# Sheet1.net
KiCad netlist of a schematic drawn in Altium Designer
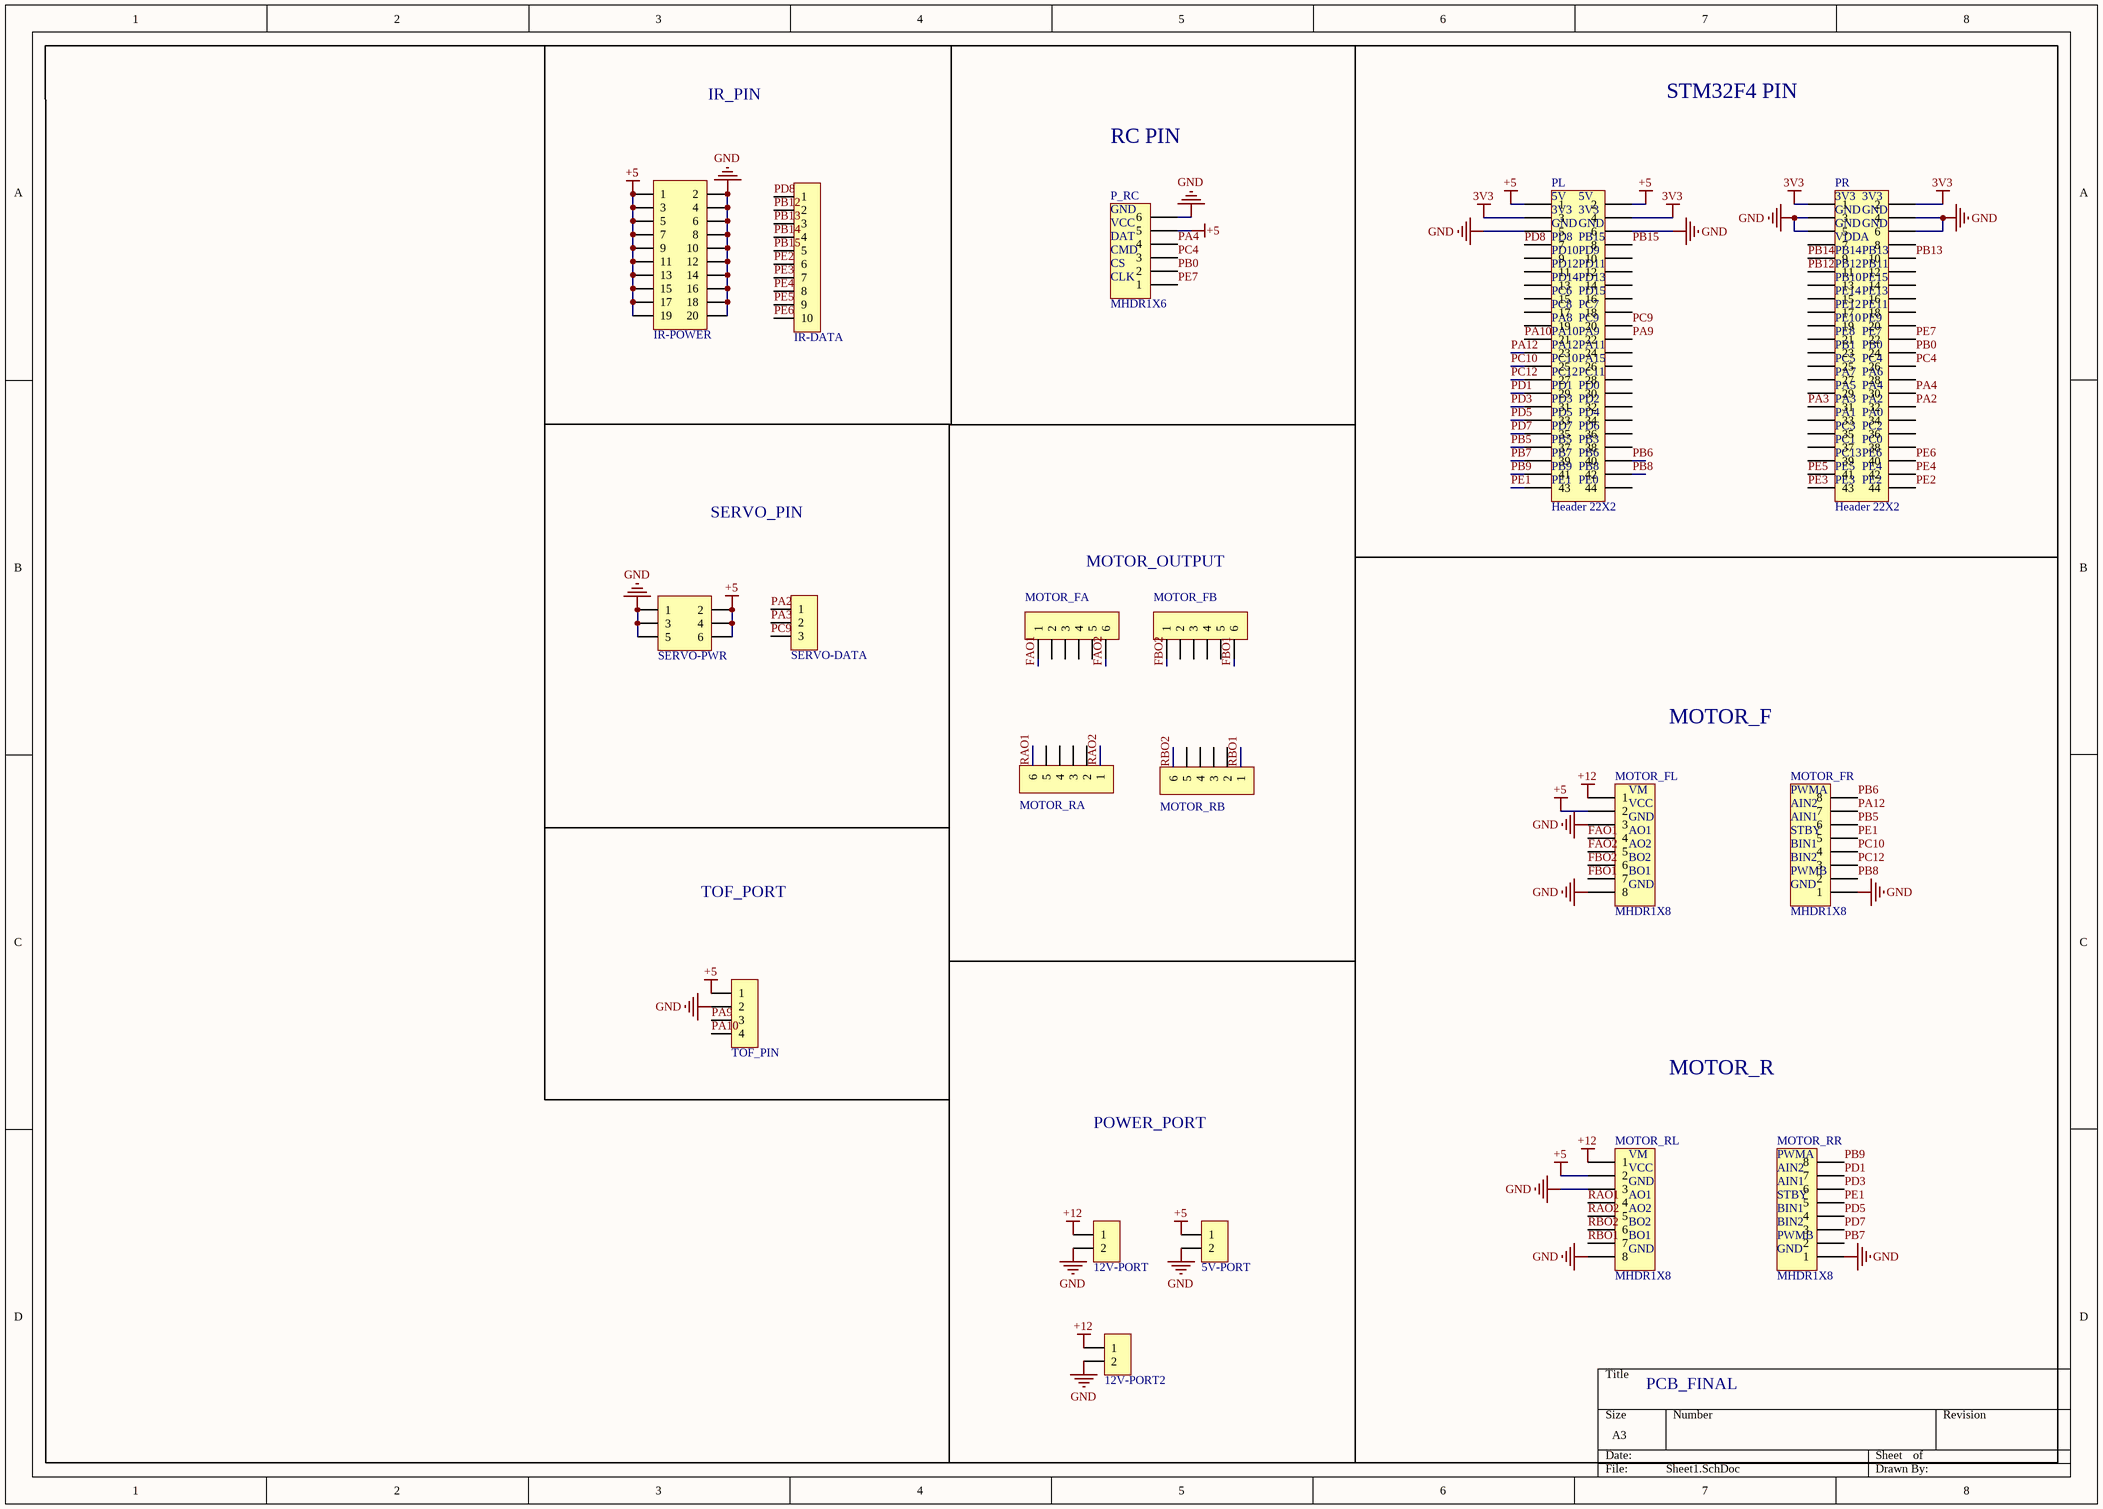
[diagram p0: Sheet1.SchDoc]

(export (version "E")
  (design (tool "Eeschema 10.0.6"))
  (components
    (comp (ref "5V-PORT")
      (value "HDR-1X2")
      (footprint "KF301-5.0-2P")
      (description "2P接插件")
      (fields (field (name "版权归属") "封装库来自淘宝卖家 ID：黄晶宝石"))
      (libsource (lib "6.1 - 接插件-脚距5.08 (200mil) ") (part "Header 2"))
    )
    (comp (ref "12V-PORT")
      (value "HDR-1X2")
      (footprint "KF301-5.0-2P")
      (description "2P接插件")
      (fields (field (name "版权归属") "封装库来自淘宝卖家 ID：黄晶宝石"))
      (libsource (lib "6.1 - 接插件-脚距5.08 (200mil) ") (part "Header 2"))
    )
    (comp (ref "12V-PORT2")
      (value "HDR-1X2")
      (footprint "KF301-5.0-2P")
      (description "2P接插件")
      (fields (field (name "版权归属") "封装库来自淘宝卖家 ID：黄晶宝石"))
      (libsource (lib "6.1 - 接插件-脚距5.08 (200mil) ") (part "Header 2"))
    )
    (comp (ref "IR-DATA")
      (value "HDR-1X10")
      (footprint "HDR2.54-LI-10P")
      (description "10P接插件")
      (fields (field (name "版权归属") "淘宝ID:黄晶宝石"))
      (libsource (lib "5.4 - 接插件-脚距2.54 (100mil) ") (part "Header 10"))
    )
    (comp (ref "IR-POWER")
      (value "Header 2X10")
      (footprint "HDR2.54-LI-2x10P")
      (description "10*2P接插件")
      (fields (field (name "版权归属") "源创客"))
      (libsource (lib "5.4 - 接插件-脚距2.54 (100mil) ") (part "Header 10X2"))
    )
    (comp (ref "MOTOR_FA")
      (value "HDR-1X6")
      (footprint "PH2.0-LI-6P")
      (description "6P接插件")
      (libsource (lib "") (part "Header 6_1"))
    )
    (comp (ref "MOTOR_FB")
      (value "HDR-1X6")
      (footprint "PH2.0-LI-6P")
      (description "6P接插件")
      (libsource (lib "") (part "Header 6_1"))
    )
    (comp (ref "MOTOR_FL")
      (value "MHDR1X8")
      (footprint "HDR2.54-M-LI-8P")
      (description "Header, 8-Pin")
      (fields (field (name "PUBLISHER") "Altium Limited"))
      (libsource (lib "Miscellaneous Connectors") (part "MHDR1X8"))
    )
    (comp (ref "MOTOR_FR")
      (value "MHDR1X8")
      (footprint "HDR2.54-M-LI-8P")
      (description "Header, 8-Pin")
      (fields (field (name "PUBLISHER") "Altium Limited"))
      (libsource (lib "") (part "MHDR1X8_1"))
    )
    (comp (ref "MOTOR_RA")
      (value "HDR-1X6")
      (footprint "PH2.0-LI-6P")
      (description "6P接插件")
      (libsource (lib "5.3 - 接插件-脚距2.0") (part "Header 6"))
    )
    (comp (ref "MOTOR_RB")
      (value "HDR-1X6")
      (footprint "PH2.0-LI-6P")
      (description "6P接插件")
      (libsource (lib "5.3 - 接插件-脚距2.0") (part "Header 6"))
    )
    (comp (ref "MOTOR_RL")
      (value "MHDR1X8")
      (footprint "HDR2.54-M-LI-8P")
      (description "Header, 8-Pin")
      (fields (field (name "PUBLISHER") "Altium Limited"))
      (libsource (lib "Miscellaneous Connectors") (part "MHDR1X8"))
    )
    (comp (ref "MOTOR_RR")
      (value "MHDR1X8")
      (footprint "HDR2.54-M-LI-8P")
      (description "Header, 8-Pin")
      (fields (field (name "PUBLISHER") "Altium Limited"))
      (libsource (lib "") (part "MHDR1X8_1"))
    )
    (comp (ref "PL")
      (value "Header 22X2")
      (footprint "P_M_2x22P")
      (description "Header, 22-Pin, Dual row")
      (fields (field (name "PUBLISHER") "Altium Limited"))
      (libsource (lib "Miscellaneous Connectors") (part "Header 22X2"))
    )
    (comp (ref "PR")
      (value "Header 22X2")
      (footprint "P_M_2x22P")
      (description "Header, 22-Pin, Dual row")
      (fields (field (name "PUBLISHER") "Altium Limited"))
      (libsource (lib "Miscellaneous Connectors") (part "Header 22X2"))
    )
    (comp (ref "P_RC")
      (value "MHDR1X6")
      (footprint "4.02-2.54mm排针-排母:HDR2.54-M-LI-6P")
      (description "Header, 6-Pin")
      (fields (field (name "PUBLISHER") "Altium Limited"))
      (libsource (lib "Miscellaneous Connectors") (part "MHDR1X6"))
    )
    (comp (ref "SERVO-DATA")
      (value "HDR-1X3")
      (footprint "HDR2.54-LI-3P")
      (description "3P接插件")
      (fields (field (name "版权归属") "封装库来自淘宝 ID：黄晶宝石"))
      (libsource (lib "5.4 - 接插件-脚距2.54 (100mil) ") (part "Header 3"))
    )
    (comp (ref "SERVO-PWR")
      (value "Header3X2")
      (footprint "HDR2.54-LI-2x3P")
      (description "3*2P接插件")
      (fields (field (name "版权归属") "封装库来自淘宝 ID：黄晶宝石"))
      (libsource (lib "5.4 - 接插件-脚距2.54 (100mil) ") (part "Header 3X2"))
    )
    (comp (ref "TOF_PIN")
      (value "HDR-1X4")
      (footprint "HDR2.54-LI-4P")
      (description "4P接插件")
      (fields (field (name "版权归属") "封装库来自淘宝 ID：黄晶宝石"))
      (libsource (lib "5.4 - 接插件-脚距2.54 (100mil) ") (part "Header 4"))
    )
  )
  (nets
    (net (code "1") (name "+5") (class "Default")
      (node (ref "5V-PORT") (pin "1") (pinfunction "1_1") (pintype "passive"))
      (node (ref "IR-POWER") (pin "1") (pinfunction "1_1") (pintype "passive"))
      (node (ref "IR-POWER") (pin "11") (pinfunction "11_11") (pintype "passive"))
      (node (ref "IR-POWER") (pin "13") (pinfunction "13_13") (pintype "passive"))
      (node (ref "IR-POWER") (pin "15") (pinfunction "15_15") (pintype "passive"))
      (node (ref "IR-POWER") (pin "17") (pinfunction "17_17") (pintype "passive"))
      (node (ref "IR-POWER") (pin "19") (pinfunction "19_19") (pintype "passive"))
      (node (ref "IR-POWER") (pin "3") (pinfunction "3_3") (pintype "passive"))
      (node (ref "IR-POWER") (pin "5") (pinfunction "5_5") (pintype "passive"))
      (node (ref "IR-POWER") (pin "7") (pinfunction "7_7") (pintype "passive"))
      (node (ref "IR-POWER") (pin "9") (pinfunction "9_9") (pintype "passive"))
      (node (ref "MOTOR_FL") (pin "2") (pinfunction "2_2") (pintype "passive"))
      (node (ref "MOTOR_RL") (pin "2") (pinfunction "2_2") (pintype "passive"))
      (node (ref "PL") (pin "1") (pinfunction "1_1") (pintype "passive"))
      (node (ref "PL") (pin "2") (pinfunction "2_2") (pintype "passive"))
      (node (ref "P_RC") (pin "5") (pinfunction "5_5") (pintype "passive"))
      (node (ref "SERVO-PWR") (pin "2") (pinfunction "2_2") (pintype "passive"))
      (node (ref "SERVO-PWR") (pin "4") (pinfunction "4_4") (pintype "passive"))
      (node (ref "SERVO-PWR") (pin "6") (pinfunction "6_6") (pintype "passive"))
      (node (ref "TOF_PIN") (pin "1") (pinfunction "1_1") (pintype "passive"))
    )
    (net (code "2") (name "+12") (class "Default")
      (node (ref "12V-PORT") (pin "1") (pinfunction "1_1") (pintype "passive"))
      (node (ref "12V-PORT2") (pin "1") (pinfunction "1_1") (pintype "passive"))
      (node (ref "MOTOR_FL") (pin "1") (pinfunction "1_1") (pintype "passive"))
      (node (ref "MOTOR_RL") (pin "1") (pinfunction "1_1") (pintype "passive"))
    )
    (net (code "3") (name "/FAO1") (class "Default")
      (node (ref "MOTOR_FA") (pin "1") (pinfunction "1_1") (pintype "passive"))
      (node (ref "MOTOR_FL") (pin "4") (pinfunction "4_4") (pintype "passive"))
    )
    (net (code "4") (name "/FAO2") (class "Default")
      (node (ref "MOTOR_FA") (pin "6") (pinfunction "6_6") (pintype "passive"))
      (node (ref "MOTOR_FL") (pin "5") (pinfunction "5_5") (pintype "passive"))
    )
    (net (code "5") (name "/FBO1") (class "Default")
      (node (ref "MOTOR_FB") (pin "6") (pinfunction "6_6") (pintype "passive"))
      (node (ref "MOTOR_FL") (pin "7") (pinfunction "7_7") (pintype "passive"))
    )
    (net (code "6") (name "/FBO2") (class "Default")
      (node (ref "MOTOR_FB") (pin "1") (pinfunction "1_1") (pintype "passive"))
      (node (ref "MOTOR_FL") (pin "6") (pinfunction "6_6") (pintype "passive"))
    )
    (net (code "7") (name "/PA2") (class "Default")
      (node (ref "PR") (pin "32") (pinfunction "32_32") (pintype "passive"))
      (node (ref "SERVO-DATA") (pin "1") (pinfunction "1_1") (pintype "passive"))
    )
    (net (code "8") (name "/PA3") (class "Default")
      (node (ref "PR") (pin "31") (pinfunction "31_31") (pintype "passive"))
      (node (ref "SERVO-DATA") (pin "2") (pinfunction "2_2") (pintype "passive"))
    )
    (net (code "9") (name "/PA4") (class "Default")
      (node (ref "PR") (pin "30") (pinfunction "30_30") (pintype "passive"))
      (node (ref "P_RC") (pin "4") (pinfunction "4_4") (pintype "passive"))
    )
    (net (code "10") (name "/PA9") (class "Default")
      (node (ref "PL") (pin "22") (pinfunction "22_22") (pintype "passive"))
      (node (ref "TOF_PIN") (pin "3") (pinfunction "3_3") (pintype "passive"))
    )
    (net (code "11") (name "/PA10") (class "Default")
      (node (ref "PL") (pin "21") (pinfunction "21_21") (pintype "passive"))
      (node (ref "TOF_PIN") (pin "4") (pinfunction "4_4") (pintype "passive"))
    )
    (net (code "12") (name "/PA12") (class "Default")
      (node (ref "MOTOR_FR") (pin "7") (pinfunction "7_7") (pintype "passive"))
      (node (ref "PL") (pin "23") (pinfunction "23_23") (pintype "passive"))
    )
    (net (code "13") (name "/PB0") (class "Default")
      (node (ref "PR") (pin "24") (pinfunction "24_24") (pintype "passive"))
      (node (ref "P_RC") (pin "2") (pinfunction "2_2") (pintype "passive"))
    )
    (net (code "14") (name "/PB5") (class "Default")
      (node (ref "MOTOR_FR") (pin "6") (pinfunction "6_6") (pintype "passive"))
      (node (ref "PL") (pin "37") (pinfunction "37_37") (pintype "passive"))
    )
    (net (code "15") (name "/PB6") (class "Default")
      (node (ref "MOTOR_FR") (pin "8") (pinfunction "8_8") (pintype "passive"))
      (node (ref "PL") (pin "40") (pinfunction "40_40") (pintype "passive"))
    )
    (net (code "16") (name "/PB7") (class "Default")
      (node (ref "MOTOR_RR") (pin "2") (pinfunction "2_2") (pintype "passive"))
      (node (ref "PL") (pin "39") (pinfunction "39_39") (pintype "passive"))
    )
    (net (code "17") (name "/PB8") (class "Default")
      (node (ref "MOTOR_FR") (pin "2") (pinfunction "2_2") (pintype "passive"))
      (node (ref "PL") (pin "42") (pinfunction "42_42") (pintype "passive"))
    )
    (net (code "18") (name "/PB9") (class "Default")
      (node (ref "MOTOR_RR") (pin "8") (pinfunction "8_8") (pintype "passive"))
      (node (ref "PL") (pin "41") (pinfunction "41_41") (pintype "passive"))
    )
    (net (code "19") (name "/PB12") (class "Default")
      (node (ref "IR-DATA") (pin "2") (pinfunction "2_2") (pintype "passive"))
      (node (ref "PR") (pin "11") (pinfunction "11_11") (pintype "passive"))
    )
    (net (code "20") (name "/PB13") (class "Default")
      (node (ref "IR-DATA") (pin "3") (pinfunction "3_3") (pintype "passive"))
      (node (ref "PR") (pin "10") (pinfunction "10_10") (pintype "passive"))
    )
    (net (code "21") (name "/PB14") (class "Default")
      (node (ref "IR-DATA") (pin "4") (pinfunction "4_4") (pintype "passive"))
      (node (ref "PR") (pin "9") (pinfunction "9_9") (pintype "passive"))
    )
    (net (code "22") (name "/PB15") (class "Default")
      (node (ref "IR-DATA") (pin "5") (pinfunction "5_5") (pintype "passive"))
      (node (ref "PL") (pin "8") (pinfunction "8_8") (pintype "passive"))
    )
    (net (code "23") (name "/PC4") (class "Default")
      (node (ref "PR") (pin "26") (pinfunction "26_26") (pintype "passive"))
      (node (ref "P_RC") (pin "3") (pinfunction "3_3") (pintype "passive"))
    )
    (net (code "24") (name "/PC9") (class "Default")
      (node (ref "PL") (pin "20") (pinfunction "20_20") (pintype "passive"))
      (node (ref "SERVO-DATA") (pin "3") (pinfunction "3_3") (pintype "passive"))
    )
    (net (code "25") (name "/PC10") (class "Default")
      (node (ref "MOTOR_FR") (pin "4") (pinfunction "4_4") (pintype "passive"))
      (node (ref "PL") (pin "25") (pinfunction "25_25") (pintype "passive"))
    )
    (net (code "26") (name "/PC12") (class "Default")
      (node (ref "MOTOR_FR") (pin "3") (pinfunction "3_3") (pintype "passive"))
      (node (ref "PL") (pin "27") (pinfunction "27_27") (pintype "passive"))
    )
    (net (code "27") (name "/PD1") (class "Default")
      (node (ref "MOTOR_RR") (pin "7") (pinfunction "7_7") (pintype "passive"))
      (node (ref "PL") (pin "29") (pinfunction "29_29") (pintype "passive"))
    )
    (net (code "28") (name "/PD3") (class "Default")
      (node (ref "MOTOR_RR") (pin "6") (pinfunction "6_6") (pintype "passive"))
      (node (ref "PL") (pin "31") (pinfunction "31_31") (pintype "passive"))
    )
    (net (code "29") (name "/PD5") (class "Default")
      (node (ref "MOTOR_RR") (pin "4") (pinfunction "4_4") (pintype "passive"))
      (node (ref "PL") (pin "33") (pinfunction "33_33") (pintype "passive"))
    )
    (net (code "30") (name "/PD7") (class "Default")
      (node (ref "MOTOR_RR") (pin "3") (pinfunction "3_3") (pintype "passive"))
      (node (ref "PL") (pin "35") (pinfunction "35_35") (pintype "passive"))
    )
    (net (code "31") (name "/PD8") (class "Default")
      (node (ref "IR-DATA") (pin "1") (pinfunction "1_1") (pintype "passive"))
      (node (ref "PL") (pin "7") (pinfunction "7_7") (pintype "passive"))
    )
    (net (code "32") (name "/PE1") (class "Default")
      (node (ref "MOTOR_FR") (pin "5") (pinfunction "5_5") (pintype "passive"))
      (node (ref "MOTOR_RR") (pin "5") (pinfunction "5_5") (pintype "passive"))
      (node (ref "PL") (pin "43") (pinfunction "43_43") (pintype "passive"))
    )
    (net (code "33") (name "/PE2") (class "Default")
      (node (ref "IR-DATA") (pin "6") (pinfunction "6_6") (pintype "passive"))
      (node (ref "PR") (pin "44") (pinfunction "44_44") (pintype "passive"))
    )
    (net (code "34") (name "/PE3") (class "Default")
      (node (ref "IR-DATA") (pin "7") (pinfunction "7_7") (pintype "passive"))
      (node (ref "PR") (pin "43") (pinfunction "43_43") (pintype "passive"))
    )
    (net (code "35") (name "/PE4") (class "Default")
      (node (ref "IR-DATA") (pin "8") (pinfunction "8_8") (pintype "passive"))
      (node (ref "PR") (pin "42") (pinfunction "42_42") (pintype "passive"))
    )
    (net (code "36") (name "/PE5") (class "Default")
      (node (ref "IR-DATA") (pin "9") (pinfunction "9_9") (pintype "passive"))
      (node (ref "PR") (pin "41") (pinfunction "41_41") (pintype "passive"))
    )
    (net (code "37") (name "/PE6") (class "Default")
      (node (ref "IR-DATA") (pin "10") (pinfunction "10_10") (pintype "passive"))
      (node (ref "PR") (pin "40") (pinfunction "40_40") (pintype "passive"))
    )
    (net (code "38") (name "/PE7") (class "Default")
      (node (ref "PR") (pin "22") (pinfunction "22_22") (pintype "passive"))
      (node (ref "P_RC") (pin "1") (pinfunction "1_1") (pintype "passive"))
    )
    (net (code "39") (name "/RAO1") (class "Default")
      (node (ref "MOTOR_RA") (pin "6") (pinfunction "6_6") (pintype "passive"))
      (node (ref "MOTOR_RL") (pin "4") (pinfunction "4_4") (pintype "passive"))
    )
    (net (code "40") (name "/RAO2") (class "Default")
      (node (ref "MOTOR_RA") (pin "1") (pinfunction "1_1") (pintype "passive"))
      (node (ref "MOTOR_RL") (pin "5") (pinfunction "5_5") (pintype "passive"))
    )
    (net (code "41") (name "/RBO1") (class "Default")
      (node (ref "MOTOR_RB") (pin "1") (pinfunction "1_1") (pintype "passive"))
      (node (ref "MOTOR_RL") (pin "7") (pinfunction "7_7") (pintype "passive"))
    )
    (net (code "42") (name "/RBO2") (class "Default")
      (node (ref "MOTOR_RB") (pin "6") (pinfunction "6_6") (pintype "passive"))
      (node (ref "MOTOR_RL") (pin "6") (pinfunction "6_6") (pintype "passive"))
    )
    (net (code "43") (name "3V3") (class "Default")
      (node (ref "PL") (pin "3") (pinfunction "3_3") (pintype "passive"))
      (node (ref "PL") (pin "4") (pinfunction "4_4") (pintype "passive"))
      (node (ref "PR") (pin "1") (pinfunction "1_1") (pintype "passive"))
      (node (ref "PR") (pin "2") (pinfunction "2_2") (pintype "passive"))
    )
    (net (code "44") (name "GND") (class "Default")
      (node (ref "12V-PORT") (pin "2") (pinfunction "2_2") (pintype "passive"))
      (node (ref "12V-PORT2") (pin "2") (pinfunction "2_2") (pintype "passive"))
      (node (ref "5V-PORT") (pin "2") (pinfunction "2_2") (pintype "passive"))
      (node (ref "IR-POWER") (pin "10") (pinfunction "10_10") (pintype "passive"))
      (node (ref "IR-POWER") (pin "12") (pinfunction "12_12") (pintype "passive"))
      (node (ref "IR-POWER") (pin "14") (pinfunction "14_14") (pintype "passive"))
      (node (ref "IR-POWER") (pin "16") (pinfunction "16_16") (pintype "passive"))
      (node (ref "IR-POWER") (pin "18") (pinfunction "18_18") (pintype "passive"))
      (node (ref "IR-POWER") (pin "2") (pinfunction "2_2") (pintype "passive"))
      (node (ref "IR-POWER") (pin "20") (pinfunction "20_20") (pintype "passive"))
      (node (ref "IR-POWER") (pin "4") (pinfunction "4_4") (pintype "passive"))
      (node (ref "IR-POWER") (pin "6") (pinfunction "6_6") (pintype "passive"))
      (node (ref "IR-POWER") (pin "8") (pinfunction "8_8") (pintype "passive"))
      (node (ref "MOTOR_FL") (pin "3") (pinfunction "3_3") (pintype "passive"))
      (node (ref "MOTOR_FL") (pin "8") (pinfunction "8_8") (pintype "passive"))
      (node (ref "MOTOR_FR") (pin "1") (pinfunction "1_1") (pintype "passive"))
      (node (ref "MOTOR_RL") (pin "3") (pinfunction "3_3") (pintype "passive"))
      (node (ref "MOTOR_RL") (pin "8") (pinfunction "8_8") (pintype "passive"))
      (node (ref "MOTOR_RR") (pin "1") (pinfunction "1_1") (pintype "passive"))
      (node (ref "PL") (pin "5") (pinfunction "5_5") (pintype "passive"))
      (node (ref "PL") (pin "6") (pinfunction "6_6") (pintype "passive"))
      (node (ref "PR") (pin "3") (pinfunction "3_3") (pintype "passive"))
      (node (ref "PR") (pin "4") (pinfunction "4_4") (pintype "passive"))
      (node (ref "PR") (pin "5") (pinfunction "5_5") (pintype "passive"))
      (node (ref "PR") (pin "6") (pinfunction "6_6") (pintype "passive"))
      (node (ref "P_RC") (pin "6") (pinfunction "6_6") (pintype "passive"))
      (node (ref "SERVO-PWR") (pin "1") (pinfunction "1_1") (pintype "passive"))
      (node (ref "SERVO-PWR") (pin "3") (pinfunction "3_3") (pintype "passive"))
      (node (ref "SERVO-PWR") (pin "5") (pinfunction "5_5") (pintype "passive"))
      (node (ref "TOF_PIN") (pin "2") (pinfunction "2_2") (pintype "passive"))
    )
    (net (code "45") (name "unconnected-(MOTOR_FA-Pad2)") (class "Default")
      (node (ref "MOTOR_FA") (pin "2") (pinfunction "2_2") (pintype "passive"))
    )
    (net (code "46") (name "unconnected-(MOTOR_FA-Pad3)") (class "Default")
      (node (ref "MOTOR_FA") (pin "3") (pinfunction "3_3") (pintype "passive"))
    )
    (net (code "47") (name "unconnected-(MOTOR_FA-Pad4)") (class "Default")
      (node (ref "MOTOR_FA") (pin "4") (pinfunction "4_4") (pintype "passive"))
    )
    (net (code "48") (name "unconnected-(MOTOR_FA-Pad5)") (class "Default")
      (node (ref "MOTOR_FA") (pin "5") (pinfunction "5_5") (pintype "passive"))
    )
    (net (code "49") (name "unconnected-(MOTOR_FB-Pad2)") (class "Default")
      (node (ref "MOTOR_FB") (pin "2") (pinfunction "2_2") (pintype "passive"))
    )
    (net (code "50") (name "unconnected-(MOTOR_FB-Pad3)") (class "Default")
      (node (ref "MOTOR_FB") (pin "3") (pinfunction "3_3") (pintype "passive"))
    )
    (net (code "51") (name "unconnected-(MOTOR_FB-Pad4)") (class "Default")
      (node (ref "MOTOR_FB") (pin "4") (pinfunction "4_4") (pintype "passive"))
    )
    (net (code "52") (name "unconnected-(MOTOR_FB-Pad5)") (class "Default")
      (node (ref "MOTOR_FB") (pin "5") (pinfunction "5_5") (pintype "passive"))
    )
    (net (code "53") (name "unconnected-(MOTOR_RA-Pad2)") (class "Default")
      (node (ref "MOTOR_RA") (pin "2") (pinfunction "2_2") (pintype "passive"))
    )
    (net (code "54") (name "unconnected-(MOTOR_RA-Pad3)") (class "Default")
      (node (ref "MOTOR_RA") (pin "3") (pinfunction "3_3") (pintype "passive"))
    )
    (net (code "55") (name "unconnected-(MOTOR_RA-Pad4)") (class "Default")
      (node (ref "MOTOR_RA") (pin "4") (pinfunction "4_4") (pintype "passive"))
    )
    (net (code "56") (name "unconnected-(MOTOR_RA-Pad5)") (class "Default")
      (node (ref "MOTOR_RA") (pin "5") (pinfunction "5_5") (pintype "passive"))
    )
    (net (code "57") (name "unconnected-(MOTOR_RB-Pad2)") (class "Default")
      (node (ref "MOTOR_RB") (pin "2") (pinfunction "2_2") (pintype "passive"))
    )
    (net (code "58") (name "unconnected-(MOTOR_RB-Pad3)") (class "Default")
      (node (ref "MOTOR_RB") (pin "3") (pinfunction "3_3") (pintype "passive"))
    )
    (net (code "59") (name "unconnected-(MOTOR_RB-Pad4)") (class "Default")
      (node (ref "MOTOR_RB") (pin "4") (pinfunction "4_4") (pintype "passive"))
    )
    (net (code "60") (name "unconnected-(MOTOR_RB-Pad5)") (class "Default")
      (node (ref "MOTOR_RB") (pin "5") (pinfunction "5_5") (pintype "passive"))
    )
    (net (code "61") (name "unconnected-(PL-Pad9)") (class "Default")
      (node (ref "PL") (pin "9") (pinfunction "9_9") (pintype "passive"))
    )
    (net (code "62") (name "unconnected-(PL-Pad10)") (class "Default")
      (node (ref "PL") (pin "10") (pinfunction "10_10") (pintype "passive"))
    )
    (net (code "63") (name "unconnected-(PL-Pad11)") (class "Default")
      (node (ref "PL") (pin "11") (pinfunction "11_11") (pintype "passive"))
    )
    (net (code "64") (name "unconnected-(PL-Pad12)") (class "Default")
      (node (ref "PL") (pin "12") (pinfunction "12_12") (pintype "passive"))
    )
    (net (code "65") (name "unconnected-(PL-Pad13)") (class "Default")
      (node (ref "PL") (pin "13") (pinfunction "13_13") (pintype "passive"))
    )
    (net (code "66") (name "unconnected-(PL-Pad14)") (class "Default")
      (node (ref "PL") (pin "14") (pinfunction "14_14") (pintype "passive"))
    )
    (net (code "67") (name "unconnected-(PL-Pad15)") (class "Default")
      (node (ref "PL") (pin "15") (pinfunction "15_15") (pintype "passive"))
    )
    (net (code "68") (name "unconnected-(PL-Pad16)") (class "Default")
      (node (ref "PL") (pin "16") (pinfunction "16_16") (pintype "passive"))
    )
    (net (code "69") (name "unconnected-(PL-Pad17)") (class "Default")
      (node (ref "PL") (pin "17") (pinfunction "17_17") (pintype "passive"))
    )
    (net (code "70") (name "unconnected-(PL-Pad18)") (class "Default")
      (node (ref "PL") (pin "18") (pinfunction "18_18") (pintype "passive"))
    )
    (net (code "71") (name "unconnected-(PL-Pad19)") (class "Default")
      (node (ref "PL") (pin "19") (pinfunction "19_19") (pintype "passive"))
    )
    (net (code "72") (name "unconnected-(PL-Pad24)") (class "Default")
      (node (ref "PL") (pin "24") (pinfunction "24_24") (pintype "passive"))
    )
    (net (code "73") (name "unconnected-(PL-Pad26)") (class "Default")
      (node (ref "PL") (pin "26") (pinfunction "26_26") (pintype "passive"))
    )
    (net (code "74") (name "unconnected-(PL-Pad28)") (class "Default")
      (node (ref "PL") (pin "28") (pinfunction "28_28") (pintype "passive"))
    )
    (net (code "75") (name "unconnected-(PL-Pad30)") (class "Default")
      (node (ref "PL") (pin "30") (pinfunction "30_30") (pintype "passive"))
    )
    (net (code "76") (name "unconnected-(PL-Pad32)") (class "Default")
      (node (ref "PL") (pin "32") (pinfunction "32_32") (pintype "passive"))
    )
    (net (code "77") (name "unconnected-(PL-Pad34)") (class "Default")
      (node (ref "PL") (pin "34") (pinfunction "34_34") (pintype "passive"))
    )
    (net (code "78") (name "unconnected-(PL-Pad36)") (class "Default")
      (node (ref "PL") (pin "36") (pinfunction "36_36") (pintype "passive"))
    )
    (net (code "79") (name "unconnected-(PL-Pad38)") (class "Default")
      (node (ref "PL") (pin "38") (pinfunction "38_38") (pintype "passive"))
    )
    (net (code "80") (name "unconnected-(PL-Pad44)") (class "Default")
      (node (ref "PL") (pin "44") (pinfunction "44_44") (pintype "passive"))
    )
    (net (code "81") (name "unconnected-(PR-Pad7)") (class "Default")
      (node (ref "PR") (pin "7") (pinfunction "7_7") (pintype "passive"))
    )
    (net (code "82") (name "unconnected-(PR-Pad8)") (class "Default")
      (node (ref "PR") (pin "8") (pinfunction "8_8") (pintype "passive"))
    )
    (net (code "83") (name "unconnected-(PR-Pad12)") (class "Default")
      (node (ref "PR") (pin "12") (pinfunction "12_12") (pintype "passive"))
    )
    (net (code "84") (name "unconnected-(PR-Pad13)") (class "Default")
      (node (ref "PR") (pin "13") (pinfunction "13_13") (pintype "passive"))
    )
    (net (code "85") (name "unconnected-(PR-Pad14)") (class "Default")
      (node (ref "PR") (pin "14") (pinfunction "14_14") (pintype "passive"))
    )
    (net (code "86") (name "unconnected-(PR-Pad15)") (class "Default")
      (node (ref "PR") (pin "15") (pinfunction "15_15") (pintype "passive"))
    )
    (net (code "87") (name "unconnected-(PR-Pad16)") (class "Default")
      (node (ref "PR") (pin "16") (pinfunction "16_16") (pintype "passive"))
    )
    (net (code "88") (name "unconnected-(PR-Pad17)") (class "Default")
      (node (ref "PR") (pin "17") (pinfunction "17_17") (pintype "passive"))
    )
    (net (code "89") (name "unconnected-(PR-Pad18)") (class "Default")
      (node (ref "PR") (pin "18") (pinfunction "18_18") (pintype "passive"))
    )
    (net (code "90") (name "unconnected-(PR-Pad19)") (class "Default")
      (node (ref "PR") (pin "19") (pinfunction "19_19") (pintype "passive"))
    )
    (net (code "91") (name "unconnected-(PR-Pad20)") (class "Default")
      (node (ref "PR") (pin "20") (pinfunction "20_20") (pintype "passive"))
    )
    (net (code "92") (name "unconnected-(PR-Pad21)") (class "Default")
      (node (ref "PR") (pin "21") (pinfunction "21_21") (pintype "passive"))
    )
    (net (code "93") (name "unconnected-(PR-Pad23)") (class "Default")
      (node (ref "PR") (pin "23") (pinfunction "23_23") (pintype "passive"))
    )
    (net (code "94") (name "unconnected-(PR-Pad25)") (class "Default")
      (node (ref "PR") (pin "25") (pinfunction "25_25") (pintype "passive"))
    )
    (net (code "95") (name "unconnected-(PR-Pad27)") (class "Default")
      (node (ref "PR") (pin "27") (pinfunction "27_27") (pintype "passive"))
    )
    (net (code "96") (name "unconnected-(PR-Pad28)") (class "Default")
      (node (ref "PR") (pin "28") (pinfunction "28_28") (pintype "passive"))
    )
    (net (code "97") (name "unconnected-(PR-Pad29)") (class "Default")
      (node (ref "PR") (pin "29") (pinfunction "29_29") (pintype "passive"))
    )
    (net (code "98") (name "unconnected-(PR-Pad33)") (class "Default")
      (node (ref "PR") (pin "33") (pinfunction "33_33") (pintype "passive"))
    )
    (net (code "99") (name "unconnected-(PR-Pad34)") (class "Default")
      (node (ref "PR") (pin "34") (pinfunction "34_34") (pintype "passive"))
    )
    (net (code "100") (name "unconnected-(PR-Pad35)") (class "Default")
      (node (ref "PR") (pin "35") (pinfunction "35_35") (pintype "passive"))
    )
    (net (code "101") (name "unconnected-(PR-Pad36)") (class "Default")
      (node (ref "PR") (pin "36") (pinfunction "36_36") (pintype "passive"))
    )
    (net (code "102") (name "unconnected-(PR-Pad37)") (class "Default")
      (node (ref "PR") (pin "37") (pinfunction "37_37") (pintype "passive"))
    )
    (net (code "103") (name "unconnected-(PR-Pad38)") (class "Default")
      (node (ref "PR") (pin "38") (pinfunction "38_38") (pintype "passive"))
    )
    (net (code "104") (name "unconnected-(PR-Pad39)") (class "Default")
      (node (ref "PR") (pin "39") (pinfunction "39_39") (pintype "passive"))
    )
  )
)
